# utilidong-test-OR-1_1.net
KiCad netlist of a schematic drawn in EAGLE
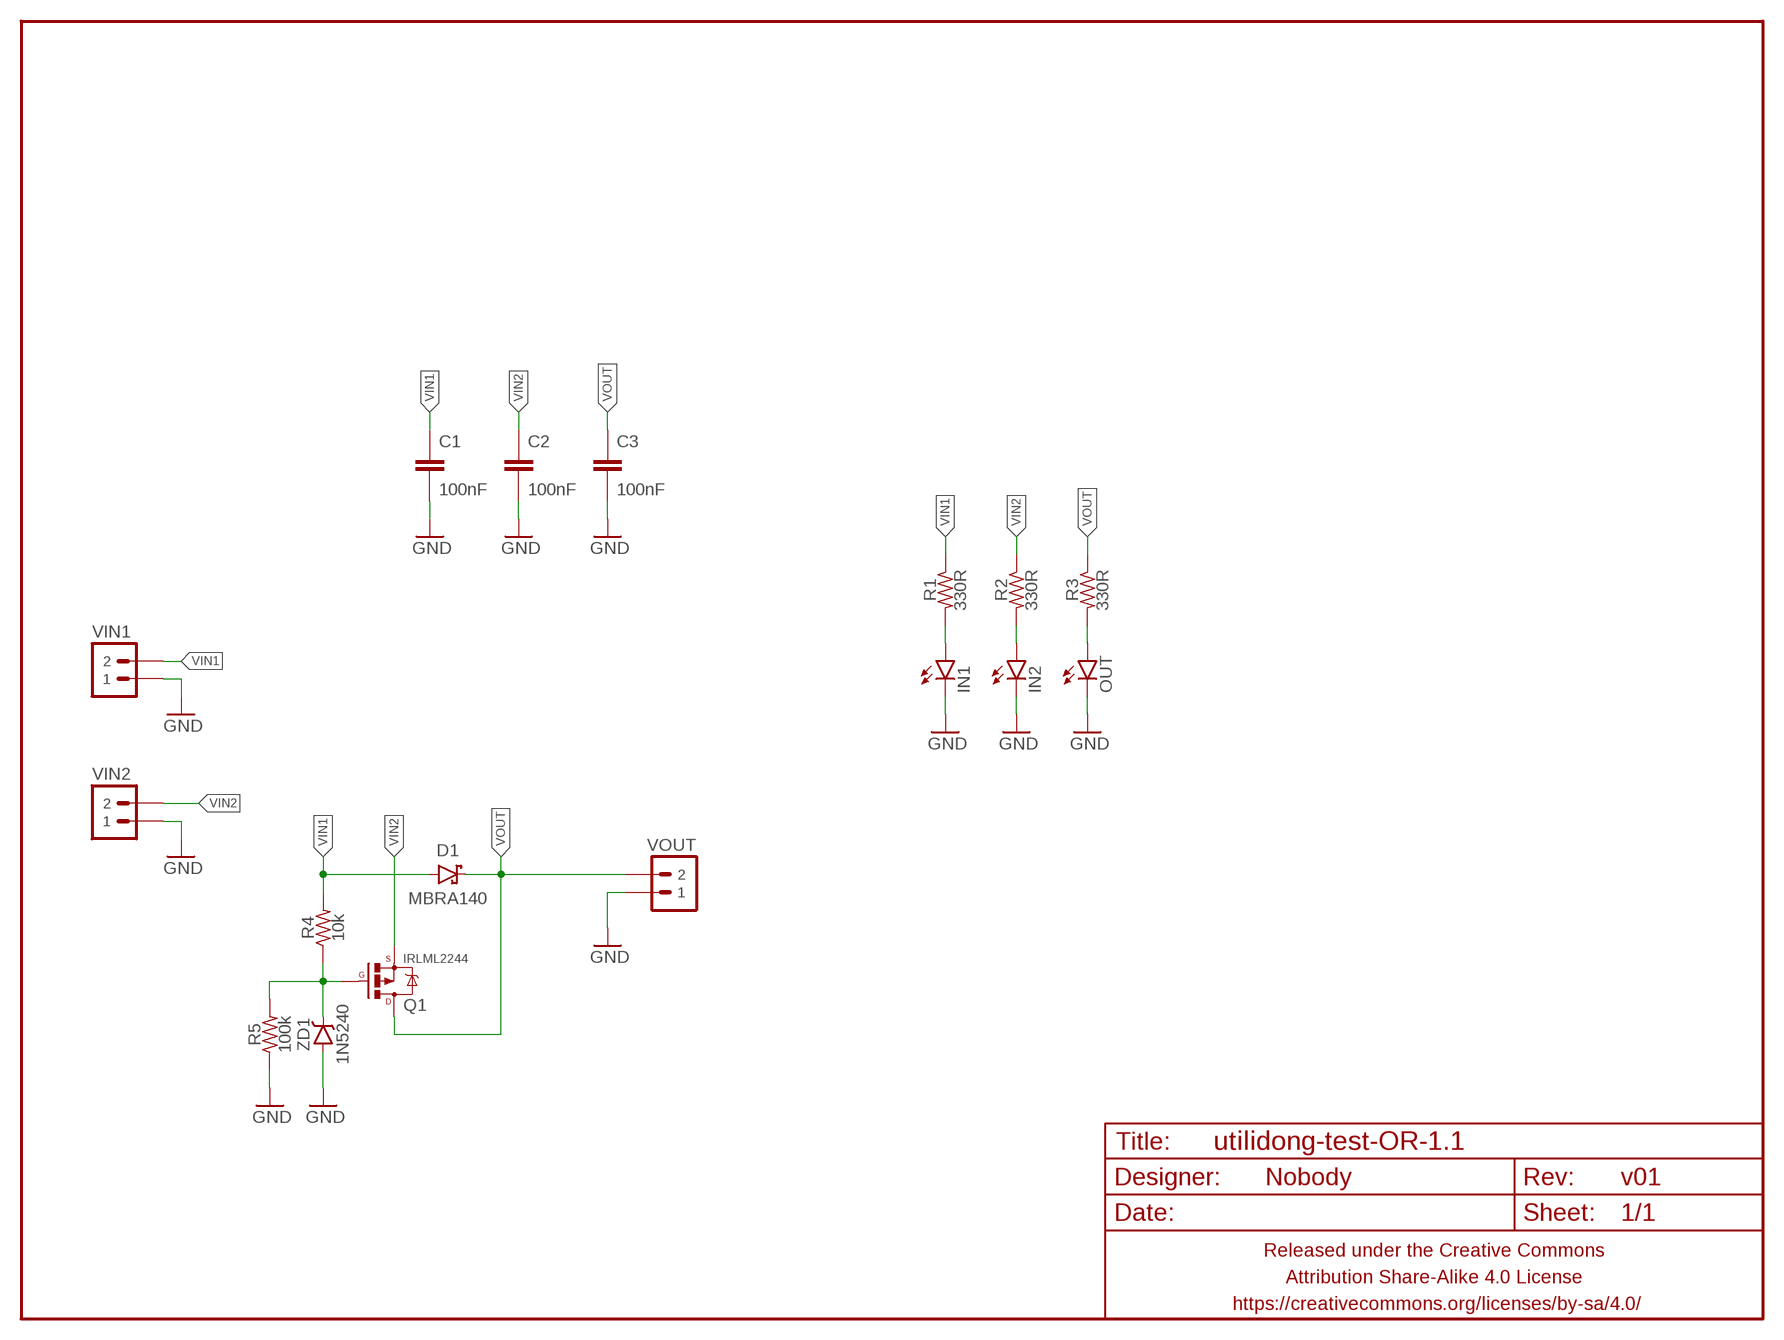
[diagram p0: schematic, sheet 1]

(export (version "E")
  (design (tool "Eeschema 10.0.6"))
  (components
    (comp (ref "C1")
      (value "100nF")
      (footprint "eagle-import:C0805")
      (libsource (lib "eagle-import") (part "CAPACITOR-CERAMICC0805"))
    )
    (comp (ref "C2")
      (value "100nF")
      (footprint "eagle-import:C0805")
      (libsource (lib "eagle-import") (part "CAPACITOR-CERAMICC0805"))
    )
    (comp (ref "C3")
      (value "100nF")
      (footprint "eagle-import:C0805")
      (libsource (lib "eagle-import") (part "CAPACITOR-CERAMICC0805"))
    )
    (comp (ref "D1")
      (value "MBRA140")
      (footprint "eagle-import:SMA-DIODE")
      (libsource (lib "eagle-import") (part "DIODE-SCHOTTKYMBRA140"))
    )
    (comp (ref "FRAME1")
      (value "FRAME-LETTERNO_PACKAGE")
      (footprint "eagle-import:DUMMY")
      (fields (field (name "DESIGNER") "Nobody"))
      (libsource (lib "eagle-import") (part "FRAME-LETTERNO_PACKAGE"))
    )
    (comp (ref "IN1")
      (value "LED1206")
      (footprint "eagle-import:LED-1206")
      (libsource (lib "eagle-import") (part "LED1206"))
    )
    (comp (ref "IN2")
      (value "LED1206")
      (footprint "eagle-import:LED-1206")
      (libsource (lib "eagle-import") (part "LED1206"))
    )
    (comp (ref "OUT")
      (value "LED1206")
      (footprint "eagle-import:LED-1206")
      (libsource (lib "eagle-import") (part "LED1206"))
    )
    (comp (ref "Q1")
      (value "IRLML2244")
      (footprint "eagle-import:SOT23")
      (libsource (lib "eagle-import") (part "MOSFET-PCHANNELSOT-23"))
    )
    (comp (ref "R1")
      (value "330R")
      (footprint "eagle-import:R0805")
      (libsource (lib "eagle-import") (part "RESISTORR0805"))
    )
    (comp (ref "R2")
      (value "330R")
      (footprint "eagle-import:R0805")
      (libsource (lib "eagle-import") (part "RESISTORR0805"))
    )
    (comp (ref "R3")
      (value "330R")
      (footprint "eagle-import:R0805")
      (libsource (lib "eagle-import") (part "RESISTORR0805"))
    )
    (comp (ref "R4")
      (value "10k")
      (footprint "eagle-import:R0805")
      (libsource (lib "eagle-import") (part "RESISTORR0805"))
    )
    (comp (ref "R5")
      (value "100k")
      (footprint "eagle-import:R0805")
      (libsource (lib "eagle-import") (part "RESISTORR0805"))
    )
    (comp (ref "VIN1")
      (value "M02PTH-CENTERED-R+")
      (footprint "eagle-import:1X02-CENTER-R+")
      (libsource (lib "eagle-import") (part "M02PTH-CENTERED-R+"))
    )
    (comp (ref "VIN2")
      (value "M02PTH-CENTERED-R+")
      (footprint "eagle-import:1X02-CENTER-R+")
      (libsource (lib "eagle-import") (part "M02PTH-CENTERED-R+"))
    )
    (comp (ref "VOUT")
      (value "M02PTH-CENTERED-R+")
      (footprint "eagle-import:1X02-CENTER-R+")
      (libsource (lib "eagle-import") (part "M02PTH-CENTERED-R+"))
    )
    (comp (ref "ZD1")
      (value "1N5240")
      (footprint "eagle-import:SOT23")
      (libsource (lib "eagle-import") (part "DIODE-ZENERSOT23"))
    )
  )
  (nets
    (net (code "1") (name "GND") (class "Default")
      (node (ref "C1") (pin "2") (pinfunction "2_2") (pintype "passive"))
      (node (ref "C2") (pin "2") (pinfunction "2_2") (pintype "passive"))
      (node (ref "C3") (pin "2") (pinfunction "2_2") (pintype "passive"))
      (node (ref "IN1") (pin "C") (pinfunction "C_C") (pintype "passive"))
      (node (ref "IN2") (pin "C") (pinfunction "C_C") (pintype "passive"))
      (node (ref "OUT") (pin "C") (pinfunction "C_C") (pintype "passive"))
      (node (ref "R5") (pin "1") (pinfunction "1_1") (pintype "passive"))
      (node (ref "VIN1") (pin "1") (pinfunction "1_1") (pintype "passive"))
      (node (ref "VIN2") (pin "1") (pinfunction "1_1") (pintype "passive"))
      (node (ref "VOUT") (pin "1") (pinfunction "1_1") (pintype "passive"))
      (node (ref "ZD1") (pin "1") (pinfunction "A_1") (pintype "passive"))
      (node (ref "ZD1") (pin "2") (pinfunction "A_2") (pintype "passive"))
    )
    (net (code "2") (name "Net-(IN1-PadA)") (class "Default")
      (node (ref "IN1") (pin "A") (pinfunction "A_A") (pintype "passive"))
      (node (ref "R1") (pin "2") (pinfunction "2_2") (pintype "passive"))
    )
    (net (code "3") (name "Net-(IN2-PadA)") (class "Default")
      (node (ref "IN2") (pin "A") (pinfunction "A_A") (pintype "passive"))
      (node (ref "R2") (pin "2") (pinfunction "2_2") (pintype "passive"))
    )
    (net (code "4") (name "Net-(OUT-PadA)") (class "Default")
      (node (ref "OUT") (pin "A") (pinfunction "A_A") (pintype "passive"))
      (node (ref "R3") (pin "2") (pinfunction "2_2") (pintype "passive"))
    )
    (net (code "5") (name "Net-(Q1-G)") (class "Default")
      (node (ref "Q1") (pin "1") (pinfunction "G_1") (pintype "passive"))
      (node (ref "R4") (pin "1") (pinfunction "1_1") (pintype "passive"))
      (node (ref "R5") (pin "2") (pinfunction "2_2") (pintype "passive"))
      (node (ref "ZD1") (pin "3") (pinfunction "C_3") (pintype "passive"))
    )
    (net (code "6") (name "VIN1") (class "Default")
      (node (ref "C1") (pin "1") (pinfunction "1_1") (pintype "passive"))
      (node (ref "D1") (pin "A") (pinfunction "A_A") (pintype "passive"))
      (node (ref "R1") (pin "1") (pinfunction "1_1") (pintype "passive"))
      (node (ref "R4") (pin "2") (pinfunction "2_2") (pintype "passive"))
      (node (ref "VIN1") (pin "2") (pinfunction "2_2") (pintype "passive"))
    )
    (net (code "7") (name "VIN2") (class "Default")
      (node (ref "C2") (pin "1") (pinfunction "1_1") (pintype "passive"))
      (node (ref "Q1") (pin "2") (pinfunction "S_2") (pintype "passive"))
      (node (ref "R2") (pin "1") (pinfunction "1_1") (pintype "passive"))
      (node (ref "VIN2") (pin "2") (pinfunction "2_2") (pintype "passive"))
    )
    (net (code "8") (name "VOUT") (class "Default")
      (node (ref "C3") (pin "1") (pinfunction "1_1") (pintype "passive"))
      (node (ref "D1") (pin "C") (pinfunction "C_C") (pintype "passive"))
      (node (ref "Q1") (pin "3") (pinfunction "D_3") (pintype "passive"))
      (node (ref "R3") (pin "1") (pinfunction "1_1") (pintype "passive"))
      (node (ref "VOUT") (pin "2") (pinfunction "2_2") (pintype "passive"))
    )
  )
)
